# TEG_ver4_sheet1.net
KiCad netlist of a schematic drawn in Altium Designer
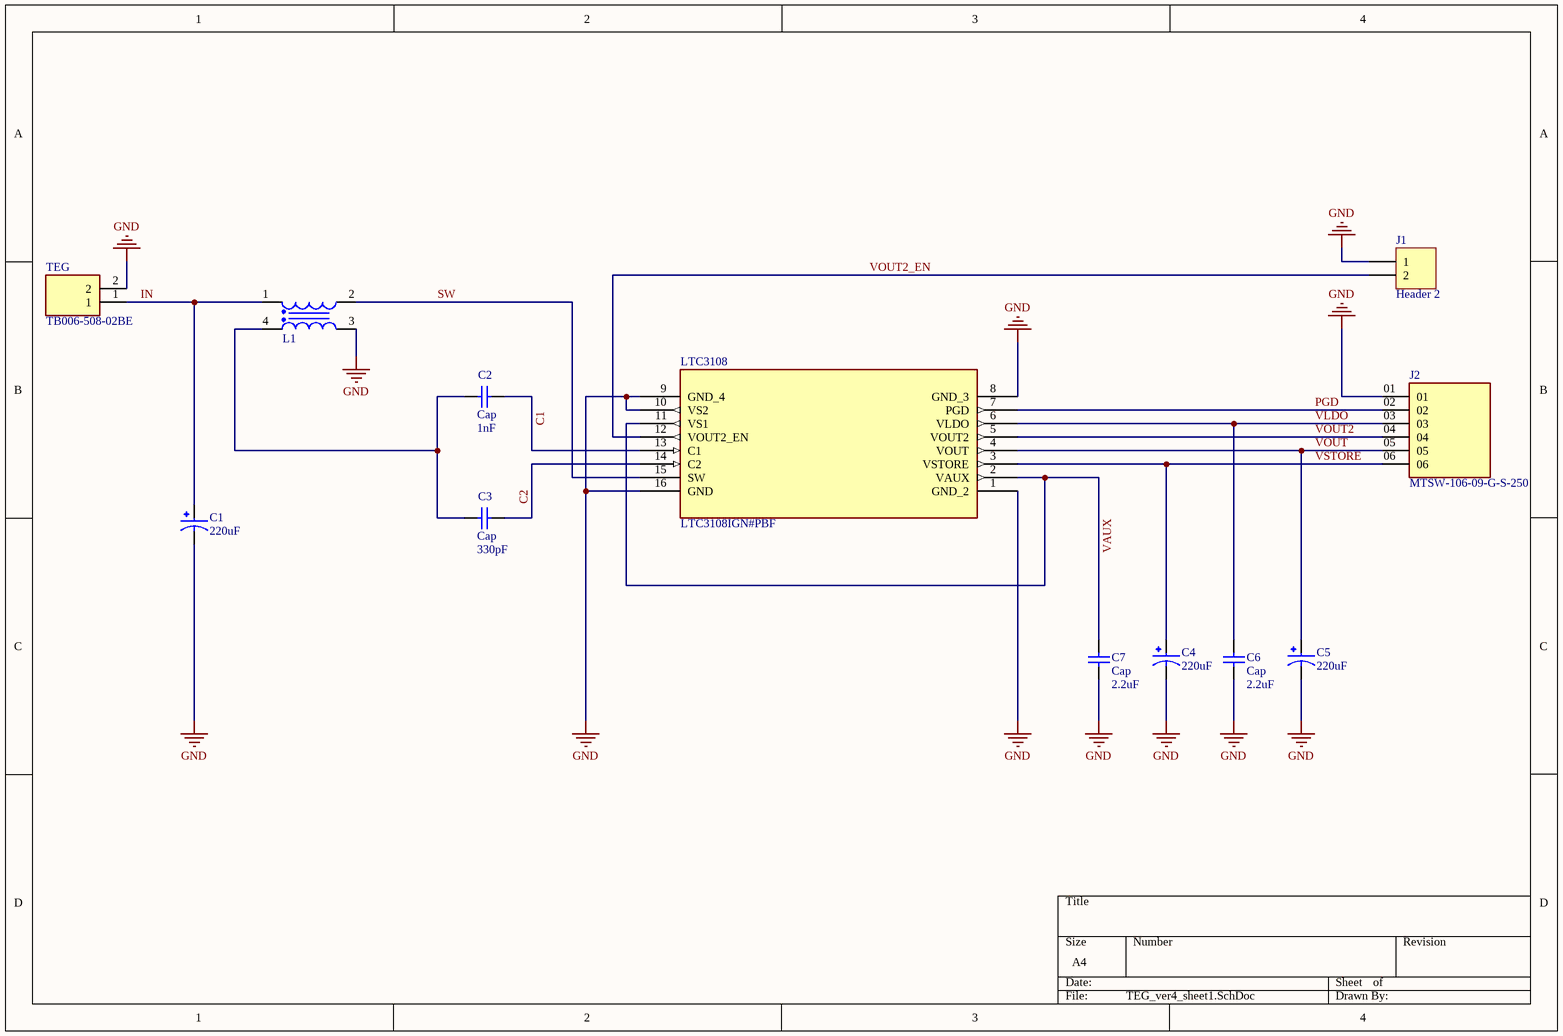
[diagram p0: TEG_ver4_sheet1.SchDoc]

(export (version "E")
  (design (tool "Eeschema 10.0.6"))
  (components
    (comp (ref "C1")
      (value "220uF")
      (footprint "CAPPRD500W50D500H1100")
      (description "Aluminum Electrolytic Capacitors, 220uF, 6.3V, -40 to 105C")
      (fields (field (name "MF") "Panasonic") (field (name "MP") "EEUFS0J221B"))
      (libsource (lib "EEUFS0J221B") (part "EEUFS0J221B"))
    )
    (comp (ref "C2")
      (value "Cap")
      (footprint "Miscellaneous Devices:RAD-0.2")
      (description "Capacitor")
      (fields (field (name "ALTIUM_VALUE") "1nF") (field (name "PUBLISHER") "Altium Limited"))
      (libsource (lib "Miscellaneous Devices") (part "Cap"))
    )
    (comp (ref "C3")
      (value "Cap")
      (footprint "Miscellaneous Devices:RAD-0.2")
      (description "Capacitor")
      (fields (field (name "ALTIUM_VALUE") "330pF") (field (name "PUBLISHER") "Altium Limited"))
      (libsource (lib "Miscellaneous Devices") (part "Cap"))
    )
    (comp (ref "C4")
      (value "220uF")
      (footprint "CAPPRD500W50D500H1100")
      (description "Aluminum Electrolytic Capacitors, 220uF, 6.3V, -40 to 105C")
      (fields (field (name "MF") "Panasonic") (field (name "MP") "EEUFS0J221B"))
      (libsource (lib "EEUFS0J221B") (part "EEUFS0J221B"))
    )
    (comp (ref "C5")
      (value "220uF")
      (footprint "CAPPRD500W50D500H1100")
      (description "Aluminum Electrolytic Capacitors, 220uF, 6.3V, -40 to 105C")
      (fields (field (name "MF") "Panasonic") (field (name "MP") "EEUFS0J221B"))
      (libsource (lib "EEUFS0J221B") (part "EEUFS0J221B"))
    )
    (comp (ref "C6")
      (value "Cap")
      (footprint "kondenzator2u2:PCBComponent_1")
      (description "Capacitor")
      (fields (field (name "ALTIUM_VALUE") "2.2uF") (field (name "PUBLISHER") "Altium Limited"))
      (libsource (lib "Miscellaneous Devices") (part "Cap"))
    )
    (comp (ref "C7")
      (value "Cap")
      (footprint "kondenzator2u2:PCBComponent_1")
      (description "Capacitor")
      (fields (field (name "ALTIUM_VALUE") "2.2uF") (field (name "PUBLISHER") "Altium Limited"))
      (libsource (lib "Miscellaneous Devices") (part "Cap"))
    )
    (comp (ref "J1")
      (value "Header 2")
      (footprint "HDR1X2")
      (description "Header, 2-Pin")
      (fields (field (name "PUBLISHER") "Altium Limited"))
      (libsource (lib "Miscellaneous Connectors") (part "Header 2"))
    )
    (comp (ref "J2")
      (value "MTSW-106-09-G-S-250")
      (footprint "SAMTEC_MTSW-106-09-G-S-250")
      (libsource (lib "MTSW-106-09-G-S-250") (part "MTSW-106-09-G-S-250"))
    )
    (comp (ref "L1")
      (value "7µH / 70000µH")
      (footprint "WE-EHPI_5838")
      (description "WE-EHPI SMT Energy Harvesting Coupled Inductor, size 5838, 7µH / 70000µH, 1:100, 1.9A")
      (fields
        (field (name "MANUFACTURER PART NUMBER") "74488540070")
        (field (name "MANUFACTURER") "Wurth Elektronik")
      )
      (libsource (lib "Altium_WE-EHPI_rev22b") (part "74488540070"))
    )
    (comp (ref "LTC3108")
      (value "LTC3108IGN#PBF")
      (footprint "zenski16pin:PCBComponent_1")
      (description "LTC3108 - Ultralow Voltage Step-Up Converter and Power Manager")
      (fields (field (name "MF") "Analog Devices"))
      (libsource (lib "LTC3108IGN_PBF") (part "LTC3108IGN#PBF"))
    )
    (comp (ref "TEG")
      (value "TB006-508-02BE")
      (footprint "CUI_TB006-508-02BE")
      (description "2~24 Poles, Screw Type, Horizontal, 5.08 Pitch, 26~14 (AWG), Terminal Block Connector")
      (fields (field (name "MF") "Same Sky"))
      (libsource (lib "TB006-508-02BE") (part "TB006-508-02BE"))
    )
  )
  (nets
    (net (code "1") (name "/C1") (class "Default")
      (node (ref "C2") (pin "2") (pinfunction "2_2") (pintype "passive"))
      (node (ref "LTC3108") (pin "13") (pinfunction "C1_13") (pintype "input"))
    )
    (net (code "2") (name "/C2") (class "Default")
      (node (ref "C3") (pin "2") (pinfunction "2_2") (pintype "passive"))
      (node (ref "LTC3108") (pin "14") (pinfunction "C2_14") (pintype "input"))
    )
    (net (code "3") (name "/IN") (class "Default")
      (node (ref "C1") (pin "P") (pinfunction "P_P") (pintype "passive"))
      (node (ref "L1") (pin "1") (pinfunction "1_1") (pintype "passive"))
      (node (ref "TEG") (pin "1") (pinfunction "1_1") (pintype "passive"))
    )
    (net (code "4") (name "/PGD") (class "Default")
      (node (ref "J2") (pin "02") (pinfunction "02_02") (pintype "passive"))
      (node (ref "LTC3108") (pin "7") (pinfunction "PGD_7") (pintype "output"))
    )
    (net (code "5") (name "/SW") (class "Default")
      (node (ref "L1") (pin "2") (pinfunction "2_2") (pintype "passive"))
      (node (ref "LTC3108") (pin "15") (pinfunction "SW_15") (pintype "passive"))
    )
    (net (code "6") (name "/VAUX") (class "Default")
      (node (ref "C7") (pin "1") (pinfunction "1_1") (pintype "passive"))
      (node (ref "LTC3108") (pin "11") (pinfunction "VS1_11") (pintype "output"))
      (node (ref "LTC3108") (pin "2") (pinfunction "VAUX_2") (pintype "output"))
    )
    (net (code "7") (name "/VLDO") (class "Default")
      (node (ref "C6") (pin "1") (pinfunction "1_1") (pintype "passive"))
      (node (ref "J2") (pin "03") (pinfunction "03_03") (pintype "passive"))
      (node (ref "LTC3108") (pin "6") (pinfunction "VLDO_6") (pintype "output"))
    )
    (net (code "8") (name "/VOUT") (class "Default")
      (node (ref "C5") (pin "P") (pinfunction "P_P") (pintype "passive"))
      (node (ref "J2") (pin "05") (pinfunction "05_05") (pintype "passive"))
      (node (ref "LTC3108") (pin "4") (pinfunction "VOUT_4") (pintype "output"))
    )
    (net (code "9") (name "/VOUT2") (class "Default")
      (node (ref "J2") (pin "04") (pinfunction "04_04") (pintype "passive"))
      (node (ref "LTC3108") (pin "5") (pinfunction "VOUT2_5") (pintype "output"))
    )
    (net (code "10") (name "/VOUT2_EN") (class "Default")
      (node (ref "J1") (pin "2") (pinfunction "2_2") (pintype "passive"))
      (node (ref "LTC3108") (pin "12") (pinfunction "VOUT2_EN_12") (pintype "output"))
    )
    (net (code "11") (name "/VSTORE") (class "Default")
      (node (ref "C4") (pin "P") (pinfunction "P_P") (pintype "passive"))
      (node (ref "J2") (pin "06") (pinfunction "06_06") (pintype "passive"))
      (node (ref "LTC3108") (pin "3") (pinfunction "VSTORE_3") (pintype "output"))
    )
    (net (code "12") (name "GND") (class "Default")
      (node (ref "C1") (pin "N") (pinfunction "N_N") (pintype "passive"))
      (node (ref "C4") (pin "N") (pinfunction "N_N") (pintype "passive"))
      (node (ref "C5") (pin "N") (pinfunction "N_N") (pintype "passive"))
      (node (ref "C6") (pin "2") (pinfunction "2_2") (pintype "passive"))
      (node (ref "C7") (pin "2") (pinfunction "2_2") (pintype "passive"))
      (node (ref "J1") (pin "1") (pinfunction "1_1") (pintype "passive"))
      (node (ref "J2") (pin "01") (pinfunction "01_01") (pintype "passive"))
      (node (ref "L1") (pin "3") (pinfunction "3_3") (pintype "passive"))
      (node (ref "LTC3108") (pin "1") (pinfunction "GND_2_1") (pintype "power_in"))
      (node (ref "LTC3108") (pin "10") (pinfunction "VS2_10") (pintype "output"))
      (node (ref "LTC3108") (pin "16") (pinfunction "GND_16") (pintype "power_in"))
      (node (ref "LTC3108") (pin "8") (pinfunction "GND_3_8") (pintype "power_in"))
      (node (ref "LTC3108") (pin "9") (pinfunction "GND_4_9") (pintype "power_in"))
      (node (ref "TEG") (pin "2") (pinfunction "2_2") (pintype "passive"))
    )
    (net (code "13") (name "Net-(C2-Pad1)") (class "Default")
      (node (ref "C2") (pin "1") (pinfunction "1_1") (pintype "passive"))
      (node (ref "C3") (pin "1") (pinfunction "1_1") (pintype "passive"))
      (node (ref "L1") (pin "4") (pinfunction "4_4") (pintype "passive"))
    )
  )
)
